# attiny_temp.net
KiCad netlist of a schematic drawn in EAGLE
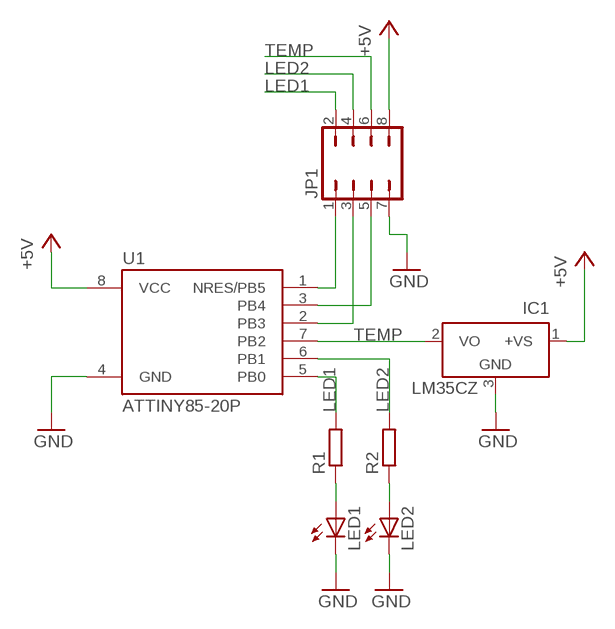
[diagram p0: schematic, sheet 1]

(export (version "E")
  (design (tool "Eeschema 10.0.6"))
  (components
    (comp (ref "IC1")
      (value "LM35CZ")
      (footprint "eagle-import:TO92")
      (libsource (lib "eagle-import") (part "LM35CZ"))
    )
    (comp (ref "JP1")
      (value "JP4Q")
      (footprint "eagle-import:JP4Q")
      (libsource (lib "eagle-import") (part "JP4Q"))
    )
    (comp (ref "LED1")
      (value "LEDCHIPLED_1206")
      (footprint "eagle-import:CHIPLED_1206")
      (libsource (lib "eagle-import") (part "LEDCHIPLED_1206"))
    )
    (comp (ref "LED2")
      (value "LEDCHIPLED_1206")
      (footprint "eagle-import:CHIPLED_1206")
      (libsource (lib "eagle-import") (part "LEDCHIPLED_1206"))
    )
    (comp (ref "R1")
      (value "R-EU_R1206")
      (footprint "eagle-import:R1206")
      (libsource (lib "eagle-import") (part "R-EU_R1206"))
    )
    (comp (ref "R2")
      (value "R-EU_R1206")
      (footprint "eagle-import:R1206")
      (libsource (lib "eagle-import") (part "R-EU_R1206"))
    )
    (comp (ref "U1")
      (value "ATTINY85-20P")
      (footprint "eagle-import:PDIP08_300MIL")
      (libsource (lib "eagle-import") (part "ATTINY85P-20"))
    )
  )
  (nets
    (net (code "1") (name "+5V") (class "Default")
      (node (ref "IC1") (pin "1") (pinfunction "+VS_1") (pintype "input"))
      (node (ref "JP1") (pin "8") (pinfunction "8_8") (pintype "passive"))
      (node (ref "U1") (pin "8") (pinfunction "VCC_8") (pintype "power_in"))
    )
    (net (code "2") (name "/LED1") (class "Default")
      (node (ref "JP1") (pin "2") (pinfunction "2_2") (pintype "passive"))
      (node (ref "R1") (pin "2") (pinfunction "2_2") (pintype "passive"))
      (node (ref "U1") (pin "5") (pinfunction "PB0_5") (pintype "bidirectional"))
    )
    (net (code "3") (name "/LED2") (class "Default")
      (node (ref "JP1") (pin "4") (pinfunction "4_4") (pintype "passive"))
      (node (ref "R2") (pin "2") (pinfunction "2_2") (pintype "passive"))
      (node (ref "U1") (pin "6") (pinfunction "PB1_6") (pintype "bidirectional"))
    )
    (net (code "4") (name "/TEMP") (class "Default")
      (node (ref "IC1") (pin "2") (pinfunction "VO_2") (pintype "input"))
      (node (ref "JP1") (pin "6") (pinfunction "6_6") (pintype "passive"))
      (node (ref "U1") (pin "7") (pinfunction "PB2_7") (pintype "bidirectional"))
    )
    (net (code "5") (name "GND") (class "Default")
      (node (ref "IC1") (pin "3") (pinfunction "GND_3") (pintype "power_in"))
      (node (ref "JP1") (pin "7") (pinfunction "7_7") (pintype "passive"))
      (node (ref "LED1") (pin "C") (pinfunction "C_C") (pintype "passive"))
      (node (ref "LED2") (pin "C") (pinfunction "C_C") (pintype "passive"))
      (node (ref "U1") (pin "4") (pinfunction "GND_4") (pintype "power_in"))
    )
    (net (code "6") (name "Net-(LED1-PadA)") (class "Default")
      (node (ref "LED1") (pin "A") (pinfunction "A_A") (pintype "passive"))
      (node (ref "R1") (pin "1") (pinfunction "1_1") (pintype "passive"))
    )
    (net (code "7") (name "Net-(LED2-PadA)") (class "Default")
      (node (ref "LED2") (pin "A") (pinfunction "A_A") (pintype "passive"))
      (node (ref "R2") (pin "1") (pinfunction "1_1") (pintype "passive"))
    )
    (net (code "8") (name "Net-(U1-NRES{slash}PB5)") (class "Default")
      (node (ref "JP1") (pin "1") (pinfunction "1_1") (pintype "passive"))
      (node (ref "U1") (pin "1") (pinfunction "NRES/PB5_1") (pintype "bidirectional"))
    )
    (net (code "9") (name "Net-(U1-PB3)") (class "Default")
      (node (ref "JP1") (pin "3") (pinfunction "3_3") (pintype "passive"))
      (node (ref "U1") (pin "2") (pinfunction "PB3_2") (pintype "bidirectional"))
    )
    (net (code "10") (name "Net-(U1-PB4)") (class "Default")
      (node (ref "JP1") (pin "5") (pinfunction "5_5") (pintype "passive"))
      (node (ref "U1") (pin "3") (pinfunction "PB4_3") (pintype "bidirectional"))
    )
  )
)
